# HEALA.net
KiCad netlist of a schematic drawn in Altium Designer
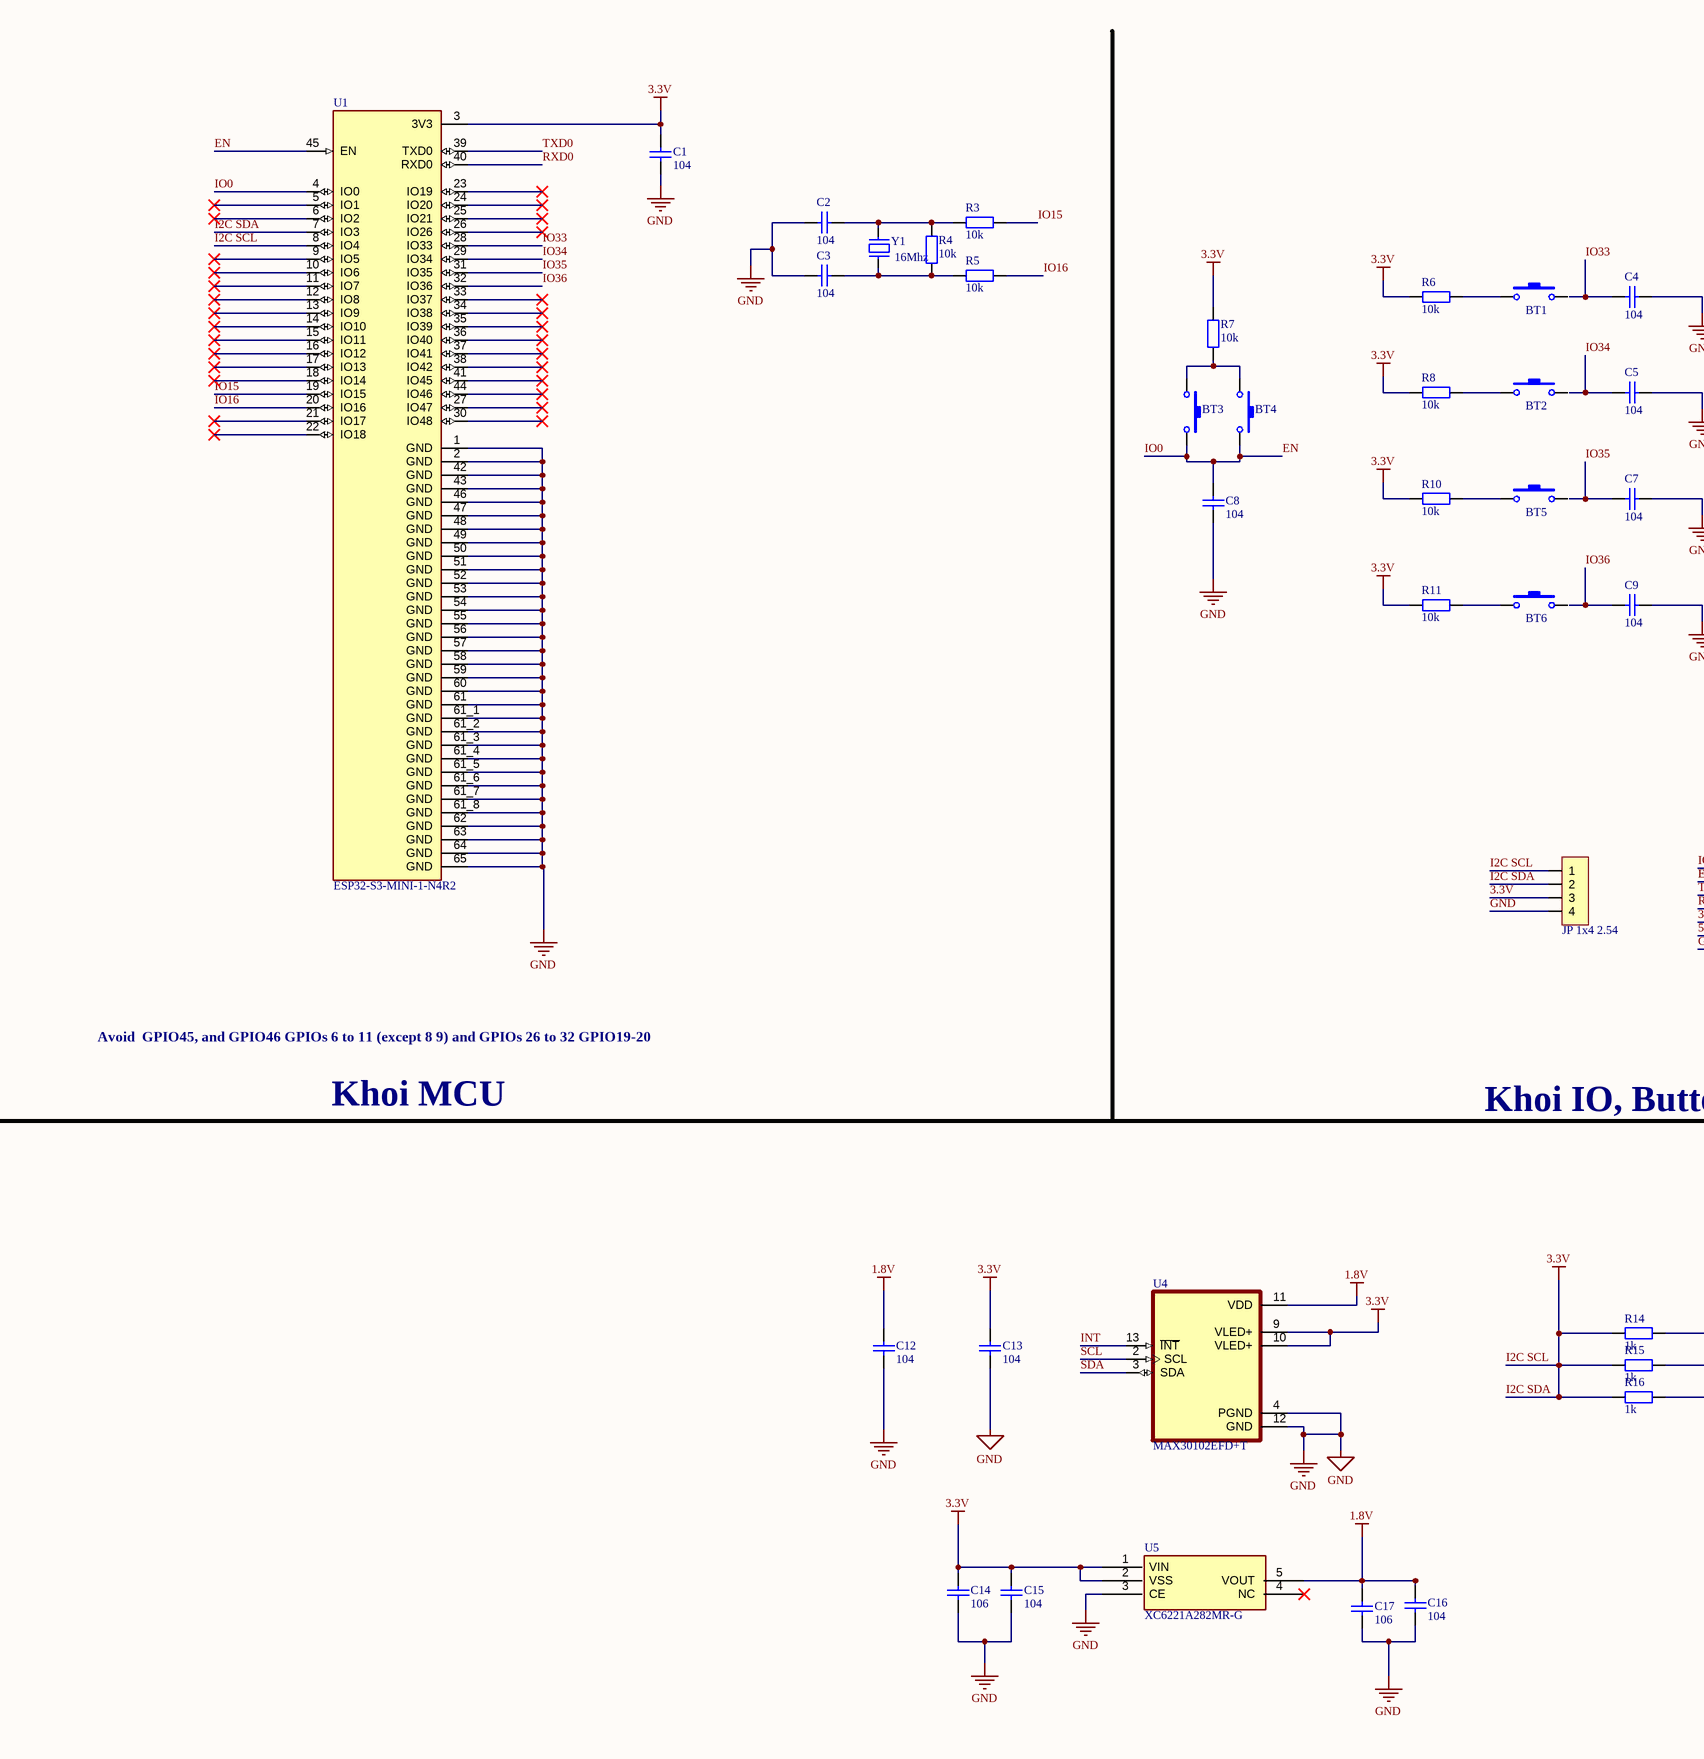
[diagram p0: HEALA.SchDoc, left]
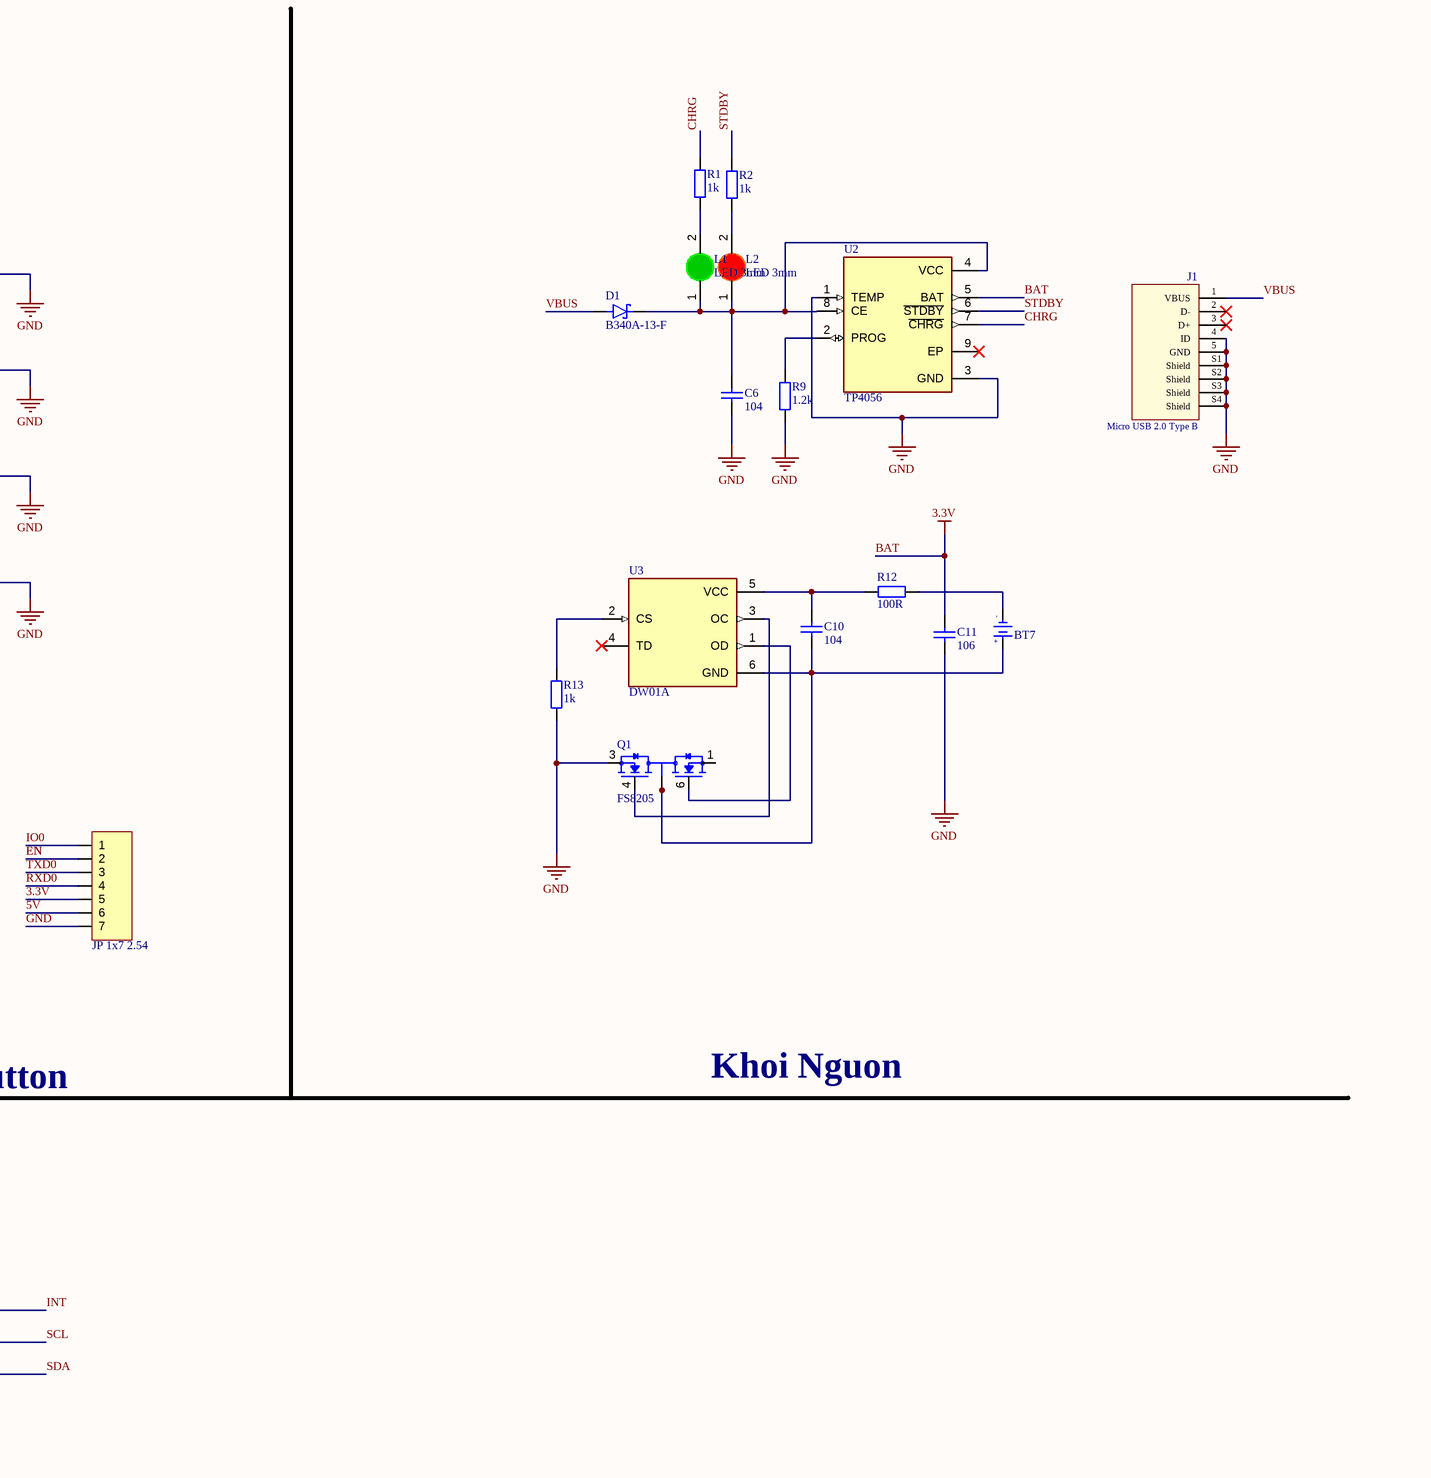
[diagram p1: HEALA.SchDoc, right]

(export (version "E")
  (design (tool "Eeschema 10.0.6"))
  (components
    (comp (ref "BT1")
      (value "Nut Nhan 2 Chan SMD 3x6x2.5")
      (footprint "Nut Nhan 2 Chan SMD 3x6x2.5")
      (libsource (lib "Component") (part "Nut Nhan 2 Chan SMD 3x6x2.5"))
    )
    (comp (ref "BT2")
      (value "Nut Nhan 2 Chan SMD 3x6x2.5")
      (footprint "Nut Nhan 2 Chan SMD 3x6x2.5")
      (libsource (lib "Component") (part "Nut Nhan 2 Chan SMD 3x6x2.5"))
    )
    (comp (ref "BT3")
      (value "Nut Nhan 2 Chan SMD 3x6x2.5")
      (footprint "Nut Nhan 2 Chan SMD 3x6x2.5")
      (libsource (lib "Component") (part "Nut Nhan 2 Chan SMD 3x6x2.5"))
    )
    (comp (ref "BT4")
      (value "Nut Nhan 2 Chan SMD 3x6x2.5")
      (footprint "Nut Nhan 2 Chan SMD 3x6x2.5")
      (libsource (lib "Component") (part "Nut Nhan 2 Chan SMD 3x6x2.5"))
    )
    (comp (ref "BT5")
      (value "Nut Nhan 2 Chan SMD 3x6x2.5")
      (footprint "Nut Nhan 2 Chan SMD 3x6x2.5")
      (libsource (lib "Component") (part "Nut Nhan 2 Chan SMD 3x6x2.5"))
    )
    (comp (ref "BT6")
      (value "Nut Nhan 2 Chan SMD 3x6x2.5")
      (footprint "Nut Nhan 2 Chan SMD 3x6x2.5")
      (libsource (lib "Component") (part "Nut Nhan 2 Chan SMD 3x6x2.5"))
    )
    (comp (ref "BT7")
      (value "NI-MH 3.6V 20mAh 3/V20H")
      (footprint "PIN 3.6V 20mAh 3/V20H")
      (description "Battery 3VDC , NI-MH 3.6V 20mAh 3/V20H")
      (libsource (lib "Component") (part "PIN 3V"))
    )
    (comp (ref "C1")
      (value "104")
      (footprint "tu 1206")
      (description "Dán")
      (libsource (lib "Capacitor") (part "Tu 1206 104 50V 20%"))
    )
    (comp (ref "C2")
      (value "104")
      (footprint "tu 1206")
      (description "Dán")
      (libsource (lib "Capacitor") (part "Tu 1206 104 50V 20%"))
    )
    (comp (ref "C3")
      (value "104")
      (footprint "tu 1206")
      (description "Dán")
      (libsource (lib "Capacitor") (part "Tu 1206 104 50V 20%"))
    )
    (comp (ref "C4")
      (value "104")
      (footprint "tu 1206")
      (description "Dán")
      (libsource (lib "Capacitor") (part "Tu 1206 104 50V 20%"))
    )
    (comp (ref "C5")
      (value "104")
      (footprint "tu 1206")
      (description "Dán")
      (libsource (lib "Capacitor") (part "Tu 1206 104 50V 20%"))
    )
    (comp (ref "C6")
      (value "104")
      (footprint "tu 0805")
      (description "Dán")
      (libsource (lib "Capacitor") (part "Tu 0805 104 50V 10%"))
    )
    (comp (ref "C7")
      (value "104")
      (footprint "tu 1206")
      (description "Dán")
      (libsource (lib "Capacitor") (part "Tu 1206 104 50V 20%"))
    )
    (comp (ref "C8")
      (value "104")
      (footprint "tu 1206")
      (description "Dán")
      (libsource (lib "Capacitor") (part "Tu 1206 104 50V 20%"))
    )
    (comp (ref "C9")
      (value "104")
      (footprint "tu 1206")
      (description "Dán")
      (libsource (lib "Capacitor") (part "Tu 1206 104 50V 20%"))
    )
    (comp (ref "C10")
      (value "104")
      (footprint "tu 1206")
      (description "Dán")
      (libsource (lib "Capacitor") (part "Tu 1206 104 50V 20%"))
    )
    (comp (ref "C11")
      (value "106")
      (footprint "tu 1206")
      (description "Dán")
      (libsource (lib "Capacitor") (part "Tu 1206 106 16V 20%"))
    )
    (comp (ref "C12")
      (value "104")
      (footprint "tu 1206")
      (description "Dán")
      (libsource (lib "Capacitor") (part "Tu 1206 104 50V 20%"))
    )
    (comp (ref "C13")
      (value "104")
      (footprint "tu 1206")
      (description "Dán")
      (libsource (lib "Capacitor") (part "Tu 1206 104 50V 20%"))
    )
    (comp (ref "C14")
      (value "106")
      (footprint "tu 1206")
      (description "Dán")
      (libsource (lib "Capacitor") (part "Tu 1206 106 16V 20%"))
    )
    (comp (ref "C15")
      (value "104")
      (footprint "tu 1206")
      (description "Dán")
      (libsource (lib "Capacitor") (part "Tu 1206 104 50V 20%"))
    )
    (comp (ref "C16")
      (value "104")
      (footprint "tu 1206")
      (description "Dán")
      (libsource (lib "Capacitor") (part "Tu 1206 104 50V 20%"))
    )
    (comp (ref "C17")
      (value "106")
      (footprint "tu 1206")
      (description "Dán")
      (libsource (lib "Capacitor") (part "Tu 1206 106 16V 20%"))
    )
    (comp (ref "D1")
      (value "B340A-13-F")
      (footprint "DIOM5226X240N")
      (description "Diode Schottky 40V 3A Surface Mount SMA")
      (fields (field (name "MF") "Diodes Inc."))
      (libsource (lib "Diode") (part "B340A-13-F"))
    )
    (comp (ref "J1")
      (value "Micro USB 2.0 Type B")
      (footprint "629105136821")
      (description "Micro USB 2.0 Type B Horizontal SMT 5 Contacts WR-COM")
      (fields (field (name "PART NUMBER") "629105136821") (field (name "PUBLISHER") "Wurth Elektronik"))
      (libsource (lib "USB") (part "629105136821"))
    )
    (comp (ref "JP1")
      (value "JP 1x7 2.54")
      (footprint "JP 1x7 CT")
      (description "Cắm")
      (libsource (lib "Jump") (part "JP 1x7 2.54 Cai Thang"))
    )
    (comp (ref "JP2")
      (value "JP 1x4 2.54")
      (footprint "JP 1x4 CT")
      (description "Cắm")
      (libsource (lib "Jump") (part "JP 1x4 2.54 Cai Thang"))
    )
    (comp (ref "L1")
      (value "LED 3mm")
      (footprint "LED-3MM-GREEN")
      (description "Cắm")
      (libsource (lib "Led") (part "LED 3mm Xanh La"))
    )
    (comp (ref "L2")
      (value "LED 3mm")
      (footprint "LED-3MM-RED")
      (description "Cắm")
      (libsource (lib "Led") (part "LED 3mm Do"))
    )
    (comp (ref "Q1")
      (value "FS8205")
      (footprint "SOT95P280X145-6N")
      (fields (field (name "MF") "Fortune Semiconductor"))
      (libsource (lib "FS8205") (part "FS8205"))
    )
    (comp (ref "R1")
      (value "1k")
      (footprint "tro smd 0603")
      (description "Dán")
      (libsource (lib "Resistor") (part "Tro 0603 1% 1k"))
    )
    (comp (ref "R2")
      (value "1k")
      (footprint "tro smd 0603")
      (description "Dán")
      (libsource (lib "Resistor") (part "Tro 0603 1% 1k"))
    )
    (comp (ref "R3")
      (value "10k")
      (footprint "tro smd 1206")
      (description "Dán")
      (libsource (lib "Resistor") (part "Tro 1206 5% 10k"))
    )
    (comp (ref "R4")
      (value "10k")
      (footprint "tro smd 1206")
      (description "Dán")
      (libsource (lib "Resistor") (part "Tro 1206 5% 10k"))
    )
    (comp (ref "R5")
      (value "10k")
      (footprint "tro smd 1206")
      (description "Dán")
      (libsource (lib "Resistor") (part "Tro 1206 5% 10k"))
    )
    (comp (ref "R6")
      (value "10k")
      (footprint "tro smd 1206")
      (description "Dán")
      (libsource (lib "Resistor") (part "Tro 1206 5% 10k"))
    )
    (comp (ref "R7")
      (value "10k")
      (footprint "tro smd 1206")
      (description "Dán")
      (libsource (lib "Resistor") (part "Tro 1206 5% 10k"))
    )
    (comp (ref "R8")
      (value "10k")
      (footprint "tro smd 1206")
      (description "Dán")
      (libsource (lib "Resistor") (part "Tro 1206 5% 10k"))
    )
    (comp (ref "R9")
      (value "1.2k")
      (footprint "tro smd 1206")
      (description "Dán")
      (libsource (lib "Resistor") (part "Tro 1206 5% 1.2k"))
    )
    (comp (ref "R10")
      (value "10k")
      (footprint "tro smd 1206")
      (description "Dán")
      (libsource (lib "Resistor") (part "Tro 1206 5% 10k"))
    )
    (comp (ref "R11")
      (value "10k")
      (footprint "tro smd 1206")
      (description "Dán")
      (libsource (lib "Resistor") (part "Tro 1206 5% 10k"))
    )
    (comp (ref "R12")
      (value "100R")
      (footprint "tro smd 1206")
      (description "Dán")
      (libsource (lib "Resistor") (part "Tro 1206 1% 100R"))
    )
    (comp (ref "R13")
      (value "1k")
      (footprint "tro smd 1206")
      (description "Dán")
      (libsource (lib "Resistor") (part "Tro 1206 5% 1k"))
    )
    (comp (ref "R14")
      (value "1k")
      (footprint "tro smd 1206")
      (description "Dán")
      (libsource (lib "Resistor") (part "Tro 1206 5% 1k"))
    )
    (comp (ref "R15")
      (value "1k")
      (footprint "tro smd 1206")
      (description "Dán")
      (libsource (lib "Resistor") (part "Tro 1206 5% 1k"))
    )
    (comp (ref "R16")
      (value "1k")
      (footprint "tro smd 1206")
      (description "Dán")
      (libsource (lib "Resistor") (part "Tro 1206 5% 1k"))
    )
    (comp (ref "U1")
      (value "ESP32-S3-MINI-1-N4R2")
      (footprint "XCVR_ESP32-S3-MINI-1-N4R2")
      (description "Bluetooth, WiFi 802.11b/g/n, Bluetooth v5.0 Transceiver Module 2.4GHz PCB Trace Surface Mount")
      (fields (field (name "MF") "Espressif Systems"))
      (libsource (lib "HEALA") (part "ESP32-S3-MINI-1-N4R2"))
    )
    (comp (ref "U2")
      (value "TP4056")
      (footprint "SOP127P600X175-9N")
      (description "Complete single cell Li-Ion battery with a constant current / constant voltage linear charger")
      (fields (field (name "MF") "NanJing Top Power ASIC Corp."))
      (libsource (lib "HEALA") (part "TP4056"))
    )
    (comp (ref "U3")
      (value "DW01A")
      (footprint "SOT95P280X145-6N")
      (description "One Cell Lithium-ion/Polymer Battery Protection IC")
      (fields (field (name "MF") "Fortune Semiconductor"))
      (libsource (lib "DW01A") (part "DW01A"))
    )
    (comp (ref "U4")
      (value "MAX30102EFD+T")
      (footprint "XDCR_MAX30101EFD+")
      (description "Pulse Oximeter and Heart Rate Sensor Digital Output")
      (fields
        (field (name "DIGI-KEY_PART_NUMBER") "MAX30102EFD+TTR-ND")
        (field (name "MF") "Maxim Integrated Products")
      )
      (libsource (lib "HEALA") (part "MAX30102EFD+T"))
    )
    (comp (ref "U5")
      (value "XC6221A282MR-G")
      (footprint "SOT95P280X120-5N")
      (libsource (lib "HEALA") (part "XC6221A282MR-G"))
    )
    (comp (ref "Y1")
      (value "16Mhz")
      (footprint "Thach Anh 2 Chan 32,768 KHz")
      (description "Crystal For all Crystal 2pin.")
      (libsource (lib "Component") (part "Thach Anh 2 chan 32,768 Khz"))
    )
  )
  (nets
    (net (code "1") (name "/5V") (class "Default")
      (node (ref "JP1") (pin "6") (pinfunction "6_6") (pintype "passive"))
    )
    (net (code "2") (name "/CHRG") (class "Default")
      (node (ref "R1") (pin "2") (pinfunction "2_2") (pintype "passive"))
      (node (ref "U2") (pin "7") (pinfunction "~{CHRG}_7") (pintype "output"))
    )
    (net (code "3") (name "/EN") (class "Default")
      (node (ref "BT3") (pin "2") (pinfunction "2_2") (pintype "passive"))
      (node (ref "BT4") (pin "2") (pinfunction "2_2") (pintype "passive"))
      (node (ref "C8") (pin "1") (pinfunction "1_1") (pintype "passive"))
      (node (ref "JP1") (pin "1") (pinfunction "1_1") (pintype "passive"))
      (node (ref "JP1") (pin "2") (pinfunction "2_2") (pintype "passive"))
      (node (ref "U1") (pin "4") (pinfunction "IO0_4") (pintype "bidirectional"))
      (node (ref "U1") (pin "45") (pinfunction "EN_45") (pintype "input"))
    )
    (net (code "4") (name "/INT") (class "Default")
      (node (ref "R14") (pin "2") (pinfunction "2_2") (pintype "passive"))
      (node (ref "U4") (pin "13") (pinfunction "~{INT}_13") (pintype "input"))
    )
    (net (code "5") (name "/IO15") (class "Default")
      (node (ref "R3") (pin "2") (pinfunction "2_2") (pintype "passive"))
      (node (ref "U1") (pin "19") (pinfunction "IO15_19") (pintype "bidirectional"))
    )
    (net (code "6") (name "/IO16") (class "Default")
      (node (ref "R5") (pin "2") (pinfunction "2_2") (pintype "passive"))
      (node (ref "U1") (pin "20") (pinfunction "IO16_20") (pintype "bidirectional"))
    )
    (net (code "7") (name "/IO33") (class "Default")
      (node (ref "C4") (pin "1") (pinfunction "1_1") (pintype "passive"))
      (node (ref "U1") (pin "28") (pinfunction "IO33_28") (pintype "bidirectional"))
    )
    (net (code "8") (name "/IO34") (class "Default")
      (node (ref "C5") (pin "1") (pinfunction "1_1") (pintype "passive"))
      (node (ref "U1") (pin "29") (pinfunction "IO34_29") (pintype "bidirectional"))
    )
    (net (code "9") (name "/IO35") (class "Default")
      (node (ref "C7") (pin "1") (pinfunction "1_1") (pintype "passive"))
      (node (ref "U1") (pin "31") (pinfunction "IO35_31") (pintype "bidirectional"))
    )
    (net (code "10") (name "/IO36") (class "Default")
      (node (ref "C9") (pin "1") (pinfunction "1_1") (pintype "passive"))
      (node (ref "U1") (pin "32") (pinfunction "IO36_32") (pintype "bidirectional"))
    )
    (net (code "11") (name "/RXD0") (class "Default")
      (node (ref "JP1") (pin "4") (pinfunction "4_4") (pintype "passive"))
      (node (ref "U1") (pin "40") (pinfunction "RXD0_40") (pintype "bidirectional"))
    )
    (net (code "12") (name "/SCL") (class "Default")
      (node (ref "R15") (pin "2") (pinfunction "2_2") (pintype "passive"))
      (node (ref "U4") (pin "2") (pinfunction "SCL_2") (pintype "input"))
    )
    (net (code "13") (name "/SDA") (class "Default")
      (node (ref "R16") (pin "2") (pinfunction "2_2") (pintype "passive"))
      (node (ref "U4") (pin "3") (pinfunction "SDA_3") (pintype "bidirectional"))
    )
    (net (code "14") (name "/STDBY") (class "Default")
      (node (ref "R2") (pin "2") (pinfunction "2_2") (pintype "passive"))
      (node (ref "U2") (pin "6") (pinfunction "~{STDBY}_6") (pintype "output"))
    )
    (net (code "15") (name "/TXD0") (class "Default")
      (node (ref "JP1") (pin "3") (pinfunction "3_3") (pintype "passive"))
      (node (ref "U1") (pin "39") (pinfunction "TXD0_39") (pintype "bidirectional"))
    )
    (net (code "16") (name "/VBUS") (class "Default")
      (node (ref "D1") (pin "A") (pinfunction "A_A") (pintype "passive"))
      (node (ref "J1") (pin "1") (pinfunction "VBUS_1") (pintype "passive"))
    )
    (net (code "17") (name "1.8V") (class "Default")
      (node (ref "C12") (pin "1") (pinfunction "1_1") (pintype "passive"))
      (node (ref "U4") (pin "11") (pinfunction "VDD_11") (pintype "power_in"))
    )
    (net (code "18") (name "3.3V") (class "Default")
      (node (ref "C1") (pin "1") (pinfunction "1_1") (pintype "passive"))
      (node (ref "C11") (pin "1") (pinfunction "1_1") (pintype "passive"))
      (node (ref "C13") (pin "1") (pinfunction "1_1") (pintype "passive"))
      (node (ref "C14") (pin "1") (pinfunction "1_1") (pintype "passive"))
      (node (ref "C15") (pin "1") (pinfunction "1_1") (pintype "passive"))
      (node (ref "JP1") (pin "5") (pinfunction "5_5") (pintype "passive"))
      (node (ref "JP2") (pin "1") (pinfunction "1_1") (pintype "passive"))
      (node (ref "JP2") (pin "2") (pinfunction "2_2") (pintype "passive"))
      (node (ref "JP2") (pin "3") (pinfunction "3_3") (pintype "passive"))
      (node (ref "R10") (pin "2") (pinfunction "2_2") (pintype "passive"))
      (node (ref "R11") (pin "2") (pinfunction "2_2") (pintype "passive"))
      (node (ref "R14") (pin "1") (pinfunction "1_1") (pintype "passive"))
      (node (ref "R15") (pin "1") (pinfunction "1_1") (pintype "passive"))
      (node (ref "R16") (pin "1") (pinfunction "1_1") (pintype "passive"))
      (node (ref "R6") (pin "2") (pinfunction "2_2") (pintype "passive"))
      (node (ref "R7") (pin "2") (pinfunction "2_2") (pintype "passive"))
      (node (ref "R8") (pin "2") (pinfunction "2_2") (pintype "passive"))
      (node (ref "U1") (pin "3") (pinfunction "3V3_3") (pintype "power_in"))
      (node (ref "U1") (pin "7") (pinfunction "IO3_7") (pintype "bidirectional"))
      (node (ref "U1") (pin "8") (pinfunction "IO4_8") (pintype "bidirectional"))
      (node (ref "U2") (pin "5") (pinfunction "BAT_5") (pintype "output"))
      (node (ref "U4") (pin "10") (pinfunction "VLED+_10") (pintype "power_in"))
      (node (ref "U4") (pin "9") (pinfunction "VLED+_9") (pintype "power_in"))
      (node (ref "U5") (pin "1") (pinfunction "VIN_1") (pintype "passive"))
      (node (ref "U5") (pin "2") (pinfunction "VSS_2") (pintype "passive"))
    )
    (net (code "19") (name "GND") (class "Default")
      (node (ref "C1") (pin "2") (pinfunction "2_2") (pintype "passive"))
      (node (ref "C11") (pin "2") (pinfunction "2_2") (pintype "passive"))
      (node (ref "C12") (pin "2") (pinfunction "2_2") (pintype "passive"))
      (node (ref "C13") (pin "2") (pinfunction "2_2") (pintype "passive"))
      (node (ref "C14") (pin "2") (pinfunction "2_2") (pintype "passive"))
      (node (ref "C15") (pin "2") (pinfunction "2_2") (pintype "passive"))
      (node (ref "C16") (pin "2") (pinfunction "2_2") (pintype "passive"))
      (node (ref "C17") (pin "2") (pinfunction "2_2") (pintype "passive"))
      (node (ref "C2") (pin "2") (pinfunction "2_2") (pintype "passive"))
      (node (ref "C3") (pin "2") (pinfunction "2_2") (pintype "passive"))
      (node (ref "C4") (pin "2") (pinfunction "2_2") (pintype "passive"))
      (node (ref "C5") (pin "2") (pinfunction "2_2") (pintype "passive"))
      (node (ref "C6") (pin "2") (pinfunction "2_2") (pintype "passive"))
      (node (ref "C7") (pin "2") (pinfunction "2_2") (pintype "passive"))
      (node (ref "C8") (pin "2") (pinfunction "2_2") (pintype "passive"))
      (node (ref "C9") (pin "2") (pinfunction "2_2") (pintype "passive"))
      (node (ref "J1") (pin "4") (pinfunction "ID_4") (pintype "passive"))
      (node (ref "J1") (pin "5") (pinfunction "GND_5") (pintype "passive"))
      (node (ref "J1") (pin "S1") (pinfunction "Shield_S1") (pintype "passive"))
      (node (ref "J1") (pin "S2") (pinfunction "Shield_S2") (pintype "passive"))
      (node (ref "J1") (pin "S3") (pinfunction "Shield_S3") (pintype "passive"))
      (node (ref "J1") (pin "S4") (pinfunction "Shield_S4") (pintype "passive"))
      (node (ref "JP1") (pin "7") (pinfunction "7_7") (pintype "passive"))
      (node (ref "JP2") (pin "4") (pinfunction "4_4") (pintype "passive"))
      (node (ref "Q1") (pin "3") (pinfunction "S2_3") (pintype "passive"))
      (node (ref "R13") (pin "1") (pinfunction "1_1") (pintype "passive"))
      (node (ref "R9") (pin "1") (pinfunction "1_1") (pintype "passive"))
      (node (ref "U1") (pin "1") (pinfunction "GND_1") (pintype "power_in"))
      (node (ref "U1") (pin "2") (pinfunction "GND_2") (pintype "power_in"))
      (node (ref "U1") (pin "42") (pinfunction "GND_42") (pintype "power_in"))
      (node (ref "U1") (pin "43") (pinfunction "GND_43") (pintype "power_in"))
      (node (ref "U1") (pin "46") (pinfunction "GND_46") (pintype "power_in"))
      (node (ref "U1") (pin "47") (pinfunction "GND_47") (pintype "power_in"))
      (node (ref "U1") (pin "48") (pinfunction "GND_48") (pintype "power_in"))
      (node (ref "U1") (pin "49") (pinfunction "GND_49") (pintype "power_in"))
      (node (ref "U1") (pin "50") (pinfunction "GND_50") (pintype "power_in"))
      (node (ref "U1") (pin "51") (pinfunction "GND_51") (pintype "power_in"))
      (node (ref "U1") (pin "52") (pinfunction "GND_52") (pintype "power_in"))
      (node (ref "U1") (pin "53") (pinfunction "GND_53") (pintype "power_in"))
      (node (ref "U1") (pin "54") (pinfunction "GND_54") (pintype "power_in"))
      (node (ref "U1") (pin "55") (pinfunction "GND_55") (pintype "power_in"))
      (node (ref "U1") (pin "56") (pinfunction "GND_56") (pintype "power_in"))
      (node (ref "U1") (pin "57") (pinfunction "GND_57") (pintype "power_in"))
      (node (ref "U1") (pin "58") (pinfunction "GND_58") (pintype "power_in"))
      (node (ref "U1") (pin "59") (pinfunction "GND_59") (pintype "power_in"))
      (node (ref "U1") (pin "60") (pinfunction "GND_60") (pintype "power_in"))
      (node (ref "U1") (pin "61") (pinfunction "GND_61") (pintype "power_in"))
      (node (ref "U1") (pin "61_1") (pinfunction "GND_61_1") (pintype "power_in"))
      (node (ref "U1") (pin "61_2") (pinfunction "GND_61_2") (pintype "power_in"))
      (node (ref "U1") (pin "61_3") (pinfunction "GND_61_3") (pintype "power_in"))
      (node (ref "U1") (pin "61_4") (pinfunction "GND_61_4") (pintype "power_in"))
      (node (ref "U1") (pin "61_5") (pinfunction "GND_61_5") (pintype "power_in"))
      (node (ref "U1") (pin "61_6") (pinfunction "GND_61_6") (pintype "power_in"))
      (node (ref "U1") (pin "61_7") (pinfunction "GND_61_7") (pintype "power_in"))
      (node (ref "U1") (pin "61_8") (pinfunction "GND_61_8") (pintype "power_in"))
      (node (ref "U1") (pin "62") (pinfunction "GND_62") (pintype "power_in"))
      (node (ref "U1") (pin "63") (pinfunction "GND_63") (pintype "power_in"))
      (node (ref "U1") (pin "64") (pinfunction "GND_64") (pintype "power_in"))
      (node (ref "U1") (pin "65") (pinfunction "GND_65") (pintype "power_in"))
      (node (ref "U2") (pin "1") (pinfunction "TEMP_1") (pintype "input"))
      (node (ref "U2") (pin "3") (pinfunction "GND_3") (pintype "power_in"))
      (node (ref "U4") (pin "12") (pinfunction "GND_12") (pintype "power_in"))
      (node (ref "U4") (pin "4") (pinfunction "PGND_4") (pintype "power_in"))
      (node (ref "U5") (pin "3") (pinfunction "CE_3") (pintype "passive"))
    )
    (net (code "20") (name "Net-(BT1-Pad1)") (class "Default")
      (node (ref "BT1") (pin "1") (pinfunction "1_1") (pintype "passive"))
      (node (ref "R6") (pin "1") (pinfunction "1_1") (pintype "passive"))
    )
    (net (code "21") (name "Net-(BT2-Pad1)") (class "Default")
      (node (ref "BT2") (pin "1") (pinfunction "1_1") (pintype "passive"))
      (node (ref "R8") (pin "1") (pinfunction "1_1") (pintype "passive"))
    )
    (net (code "22") (name "Net-(BT3-Pad1)") (class "Default")
      (node (ref "BT3") (pin "1") (pinfunction "1_1") (pintype "passive"))
      (node (ref "BT4") (pin "1") (pinfunction "1_1") (pintype "passive"))
      (node (ref "R7") (pin "1") (pinfunction "1_1") (pintype "passive"))
    )
    (net (code "23") (name "Net-(BT5-Pad1)") (class "Default")
      (node (ref "BT5") (pin "1") (pinfunction "1_1") (pintype "passive"))
      (node (ref "R10") (pin "1") (pinfunction "1_1") (pintype "passive"))
    )
    (net (code "24") (name "Net-(BT6-Pad1)") (class "Default")
      (node (ref "BT6") (pin "1") (pinfunction "1_1") (pintype "passive"))
      (node (ref "R11") (pin "1") (pinfunction "1_1") (pintype "passive"))
    )
    (net (code "25") (name "Net-(BT7-+3V)") (class "Default")
      (node (ref "BT7") (pin "1") (pinfunction "+3V_1") (pintype "passive"))
      (node (ref "C10") (pin "2") (pinfunction "2_2") (pintype "passive"))
      (node (ref "Q1") (pin "2") (pinfunction "D12_2") (pintype "passive"))
      (node (ref "Q1") (pin "5") (pinfunction "D12_5") (pintype "passive"))
      (node (ref "U3") (pin "6") (pinfunction "GND_6") (pintype "power_in"))
    )
    (net (code "26") (name "Net-(BT7-GND)") (class "Default")
      (node (ref "BT7") (pin "2") (pinfunction "GND_2") (pintype "passive"))
      (node (ref "R12") (pin "2") (pinfunction "2_2") (pintype "passive"))
    )
    (net (code "27") (name "Net-(C2-Pad1)") (class "Default")
      (node (ref "C2") (pin "1") (pinfunction "1_1") (pintype "passive"))
      (node (ref "R3") (pin "1") (pinfunction "1_1") (pintype "passive"))
      (node (ref "R4") (pin "2") (pinfunction "2_2") (pintype "passive"))
      (node (ref "Y1") (pin "2") (pinfunction "2_2") (pintype "passive"))
    )
    (net (code "28") (name "Net-(C3-Pad1)") (class "Default")
      (node (ref "C3") (pin "1") (pinfunction "1_1") (pintype "passive"))
      (node (ref "R4") (pin "1") (pinfunction "1_1") (pintype "passive"))
      (node (ref "R5") (pin "1") (pinfunction "1_1") (pintype "passive"))
      (node (ref "Y1") (pin "1") (pinfunction "1_1") (pintype "passive"))
    )
    (net (code "29") (name "Net-(L1-A)") (class "Default")
      (node (ref "C6") (pin "1") (pinfunction "1_1") (pintype "passive"))
      (node (ref "D1") (pin "C") (pinfunction "C_C") (pintype "passive"))
      (node (ref "L1") (pin "1") (pinfunction "A_1") (pintype "passive"))
      (node (ref "L2") (pin "1") (pinfunction "A_1") (pintype "passive"))
      (node (ref "U2") (pin "4") (pinfunction "VCC_4") (pintype "power_in"))
      (node (ref "U2") (pin "8") (pinfunction "CE_8") (pintype "input"))
    )
    (net (code "30") (name "Net-(L1-K)") (class "Default")
      (node (ref "L1") (pin "2") (pinfunction "K_2") (pintype "passive"))
      (node (ref "R1") (pin "1") (pinfunction "1_1") (pintype "passive"))
    )
    (net (code "31") (name "Net-(L2-K)") (class "Default")
      (node (ref "L2") (pin "2") (pinfunction "K_2") (pintype "passive"))
      (node (ref "R2") (pin "1") (pinfunction "1_1") (pintype "passive"))
    )
    (net (code "32") (name "Net-(Q1-G1)") (class "Default")
      (node (ref "Q1") (pin "6") (pinfunction "G1_6") (pintype "passive"))
      (node (ref "U3") (pin "1") (pinfunction "OD_1") (pintype "output"))
    )
    (net (code "33") (name "Net-(Q1-G2)") (class "Default")
      (node (ref "Q1") (pin "4") (pinfunction "G2_4") (pintype "passive"))
      (node (ref "U3") (pin "3") (pinfunction "OC_3") (pintype "output"))
    )
    (net (code "34") (name "Net-(U2-PROG)") (class "Default")
      (node (ref "R9") (pin "2") (pinfunction "2_2") (pintype "passive"))
      (node (ref "U2") (pin "2") (pinfunction "PROG_2") (pintype "bidirectional"))
    )
    (net (code "35") (name "Net-(U3-CS)") (class "Default")
      (node (ref "R13") (pin "2") (pinfunction "2_2") (pintype "passive"))
      (node (ref "U3") (pin "2") (pinfunction "CS_2") (pintype "input"))
    )
    (net (code "36") (name "Net-(U3-VCC)") (class "Default")
      (node (ref "C10") (pin "1") (pinfunction "1_1") (pintype "passive"))
      (node (ref "R12") (pin "1") (pinfunction "1_1") (pintype "passive"))
      (node (ref "U3") (pin "5") (pinfunction "VCC_5") (pintype "power_in"))
    )
    (net (code "37") (name "Net-(U5-VOUT)") (class "Default")
      (node (ref "C16") (pin "1") (pinfunction "1_1") (pintype "passive"))
      (node (ref "C17") (pin "1") (pinfunction "1_1") (pintype "passive"))
      (node (ref "U5") (pin "5") (pinfunction "VOUT_5") (pintype "passive"))
    )
    (net (code "38") (name "unconnected-(BT1-Pad2)") (class "Default")
      (node (ref "BT1") (pin "2") (pinfunction "2_2") (pintype "passive"))
    )
    (net (code "39") (name "unconnected-(BT2-Pad2)") (class "Default")
      (node (ref "BT2") (pin "2") (pinfunction "2_2") (pintype "passive"))
    )
    (net (code "40") (name "unconnected-(BT5-Pad2)") (class "Default")
      (node (ref "BT5") (pin "2") (pinfunction "2_2") (pintype "passive"))
    )
    (net (code "41") (name "unconnected-(BT6-Pad2)") (class "Default")
      (node (ref "BT6") (pin "2") (pinfunction "2_2") (pintype "passive"))
    )
    (net (code "42") (name "unconnected-(J1-D+-Pad3)") (class "Default")
      (node (ref "J1") (pin "3") (pinfunction "D+_3") (pintype "passive+no_connect"))
    )
    (net (code "43") (name "unconnected-(J1-D--Pad2)") (class "Default")
      (node (ref "J1") (pin "2") (pinfunction "D-_2") (pintype "passive+no_connect"))
    )
    (net (code "44") (name "unconnected-(Q1-S1-Pad1)") (class "Default")
      (node (ref "Q1") (pin "1") (pinfunction "S1_1") (pintype "passive"))
    )
    (net (code "45") (name "unconnected-(U1-IO1-Pad5)") (class "Default")
      (node (ref "U1") (pin "5") (pinfunction "IO1_5") (pintype "bidirectional+no_connect"))
    )
    (net (code "46") (name "unconnected-(U1-IO2-Pad6)") (class "Default")
      (node (ref "U1") (pin "6") (pinfunction "IO2_6") (pintype "bidirectional+no_connect"))
    )
    (net (code "47") (name "unconnected-(U1-IO5-Pad9)") (class "Default")
      (node (ref "U1") (pin "9") (pinfunction "IO5_9") (pintype "bidirectional+no_connect"))
    )
    (net (code "48") (name "unconnected-(U1-IO6-Pad10)") (class "Default")
      (node (ref "U1") (pin "10") (pinfunction "IO6_10") (pintype "bidirectional+no_connect"))
    )
    (net (code "49") (name "unconnected-(U1-IO7-Pad11)") (class "Default")
      (node (ref "U1") (pin "11") (pinfunction "IO7_11") (pintype "bidirectional+no_connect"))
    )
    (net (code "50") (name "unconnected-(U1-IO8-Pad12)") (class "Default")
      (node (ref "U1") (pin "12") (pinfunction "IO8_12") (pintype "bidirectional+no_connect"))
    )
    (net (code "51") (name "unconnected-(U1-IO9-Pad13)") (class "Default")
      (node (ref "U1") (pin "13") (pinfunction "IO9_13") (pintype "bidirectional+no_connect"))
    )
    (net (code "52") (name "unconnected-(U1-IO10-Pad14)") (class "Default")
      (node (ref "U1") (pin "14") (pinfunction "IO10_14") (pintype "bidirectional+no_connect"))
    )
    (net (code "53") (name "unconnected-(U1-IO11-Pad15)") (class "Default")
      (node (ref "U1") (pin "15") (pinfunction "IO11_15") (pintype "bidirectional+no_connect"))
    )
    (net (code "54") (name "unconnected-(U1-IO12-Pad16)") (class "Default")
      (node (ref "U1") (pin "16") (pinfunction "IO12_16") (pintype "bidirectional+no_connect"))
    )
    (net (code "55") (name "unconnected-(U1-IO13-Pad17)") (class "Default")
      (node (ref "U1") (pin "17") (pinfunction "IO13_17") (pintype "bidirectional+no_connect"))
    )
    (net (code "56") (name "unconnected-(U1-IO14-Pad18)") (class "Default")
      (node (ref "U1") (pin "18") (pinfunction "IO14_18") (pintype "bidirectional+no_connect"))
    )
    (net (code "57") (name "unconnected-(U1-IO17-Pad21)") (class "Default")
      (node (ref "U1") (pin "21") (pinfunction "IO17_21") (pintype "bidirectional+no_connect"))
    )
    (net (code "58") (name "unconnected-(U1-IO18-Pad22)") (class "Default")
      (node (ref "U1") (pin "22") (pinfunction "IO18_22") (pintype "bidirectional+no_connect"))
    )
    (net (code "59") (name "unconnected-(U1-IO19-Pad23)") (class "Default")
      (node (ref "U1") (pin "23") (pinfunction "IO19_23") (pintype "bidirectional+no_connect"))
    )
    (net (code "60") (name "unconnected-(U1-IO20-Pad24)") (class "Default")
      (node (ref "U1") (pin "24") (pinfunction "IO20_24") (pintype "bidirectional+no_connect"))
    )
    (net (code "61") (name "unconnected-(U1-IO21-Pad25)") (class "Default")
      (node (ref "U1") (pin "25") (pinfunction "IO21_25") (pintype "bidirectional+no_connect"))
    )
    (net (code "62") (name "unconnected-(U1-IO26-Pad26)") (class "Default")
      (node (ref "U1") (pin "26") (pinfunction "IO26_26") (pintype "bidirectional+no_connect"))
    )
    (net (code "63") (name "unconnected-(U1-IO37-Pad33)") (class "Default")
      (node (ref "U1") (pin "33") (pinfunction "IO37_33") (pintype "bidirectional+no_connect"))
    )
    (net (code "64") (name "unconnected-(U1-IO38-Pad34)") (class "Default")
      (node (ref "U1") (pin "34") (pinfunction "IO38_34") (pintype "bidirectional+no_connect"))
    )
    (net (code "65") (name "unconnected-(U1-IO39-Pad35)") (class "Default")
      (node (ref "U1") (pin "35") (pinfunction "IO39_35") (pintype "bidirectional+no_connect"))
    )
    (net (code "66") (name "unconnected-(U1-IO40-Pad36)") (class "Default")
      (node (ref "U1") (pin "36") (pinfunction "IO40_36") (pintype "bidirectional+no_connect"))
    )
    (net (code "67") (name "unconnected-(U1-IO41-Pad37)") (class "Default")
      (node (ref "U1") (pin "37") (pinfunction "IO41_37") (pintype "bidirectional+no_connect"))
    )
    (net (code "68") (name "unconnected-(U1-IO42-Pad38)") (class "Default")
      (node (ref "U1") (pin "38") (pinfunction "IO42_38") (pintype "bidirectional+no_connect"))
    )
    (net (code "69") (name "unconnected-(U1-IO45-Pad41)") (class "Default")
      (node (ref "U1") (pin "41") (pinfunction "IO45_41") (pintype "bidirectional+no_connect"))
    )
    (net (code "70") (name "unconnected-(U1-IO46-Pad44)") (class "Default")
      (node (ref "U1") (pin "44") (pinfunction "IO46_44") (pintype "bidirectional+no_connect"))
    )
    (net (code "71") (name "unconnected-(U1-IO47-Pad27)") (class "Default")
      (node (ref "U1") (pin "27") (pinfunction "IO47_27") (pintype "bidirectional+no_connect"))
    )
    (net (code "72") (name "unconnected-(U1-IO48-Pad30)") (class "Default")
      (node (ref "U1") (pin "30") (pinfunction "IO48_30") (pintype "bidirectional+no_connect"))
    )
    (net (code "73") (name "unconnected-(U2-EP-Pad9)") (class "Default")
      (node (ref "U2") (pin "9") (pinfunction "EP_9") (pintype "passive+no_connect"))
    )
    (net (code "74") (name "unconnected-(U3-TD-Pad4)") (class "Default")
      (node (ref "U3") (pin "4") (pinfunction "TD_4") (pintype "passive+no_connect"))
    )
    (net (code "75") (name "unconnected-(U5-NC-Pad4)") (class "Default")
      (node (ref "U5") (pin "4") (pinfunction "NC_4") (pintype "passive+no_connect"))
    )
  )
)
